# 990207_Schematic.net
KiCad netlist of a schematic drawn in Altium Designer
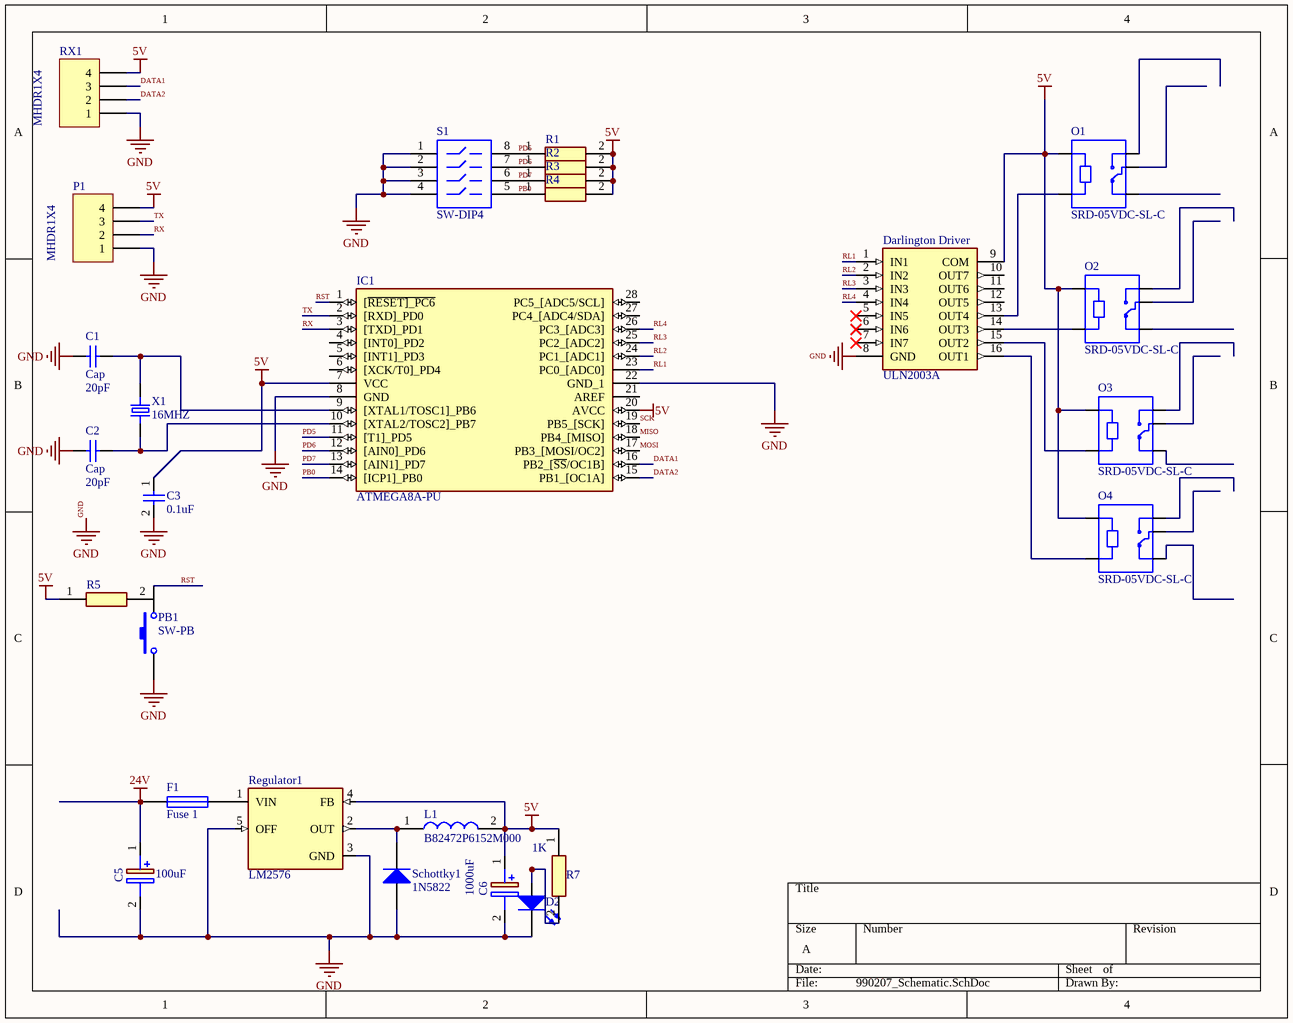
[diagram p0: 990207_Schematic.SchDoc]

(export (version "E")
  (design (tool "Eeschema 10.0.6"))
  (components
    (comp (ref "C1")
      (value "Cap")
      (footprint "RAD-0.3")
      (description "Capacitor")
      (fields (field (name "ALTIUM_VALUE") "20pF") (field (name "PUBLISHER") "Altium Limited"))
      (libsource (lib "Miscellaneous Devices") (part "Cap"))
    )
    (comp (ref "C2")
      (value "Cap")
      (footprint "RAD-0.3")
      (description "Capacitor")
      (fields (field (name "ALTIUM_VALUE") "20pF") (field (name "PUBLISHER") "Altium Limited"))
      (libsource (lib "Miscellaneous Devices") (part "Cap"))
    )
    (comp (ref "C3")
      (value "0.1uF")
      (footprint "RAD-0.3")
      (description "Capacitor")
      (fields (field (name "PUBLISHER") "Altium Limited"))
      (libsource (lib "") (part "Cap_1"))
    )
    (comp (ref "C5")
      (value "100uF")
      (footprint "SamacSys:CAPPRD550W60D1050H2150")
      (description "Capacitor Polarised")
      (fields (field (name "MANUFACTURER_PART_NUMBER") "108CKE025M"))
      (libsource (lib "*") (part "108CKE025M"))
    )
    (comp (ref "C6")
      (value "1000uF")
      (footprint "SamacSys:CAPPRD550W60D1050H2150")
      (description "Capacitor Polarised")
      (fields (field (name "MANUFACTURER_PART_NUMBER") "108CKE025M"))
      (libsource (lib "*") (part "108CKE025M"))
    )
    (comp (ref "D2")
      (value "LED0")
      (footprint "LED-0")
      (description "Typical INFRARED GaAs LED")
      (fields (field (name "PUBLISHER") "Altium Limited"))
      (libsource (lib "Miscellaneous Devices") (part "LED0"))
    )
    (comp (ref "Darlington Driver")
      (value "ULN2003A")
      (footprint "SamacSys:DIP794W56P254L1918H533Q16N")
      (description "Integrated Circuit")
      (fields (field (name "MOUSER PART NUMBER") "511-ULN2003A") (field (name "RS PART NUMBER") "6868209"))
      (libsource (lib "*") (part "ULN2003A"))
    )
    (comp (ref "F1")
      (value "Fuse 1")
      (footprint "PIN-W2/E2.8")
      (description "Fuse")
      (fields (field (name "PUBLISHER") "Altium Limited"))
      (libsource (lib "Miscellaneous Devices") (part "Fuse 1"))
    )
    (comp (ref "IC1")
      (value "ATMEGA8A-PU")
      (footprint "SamacSys:DIP794W53P254L3467H457Q28N")
      (description "Integrated Circuit")
      (fields
        (field (name "MOUSER PART NUMBER") "556-ATMEGA8A-PU")
        (field (name "RS PART NUMBER") "1310372P")
      )
      (libsource (lib "*") (part "ATMEGA8A-PU"))
    )
    (comp (ref "L1")
      (value "B82472P6152M000")
      (footprint "SamacSys:INDPM7474X450N")
      (description "Inductor")
      (fields (field (name "MOUSER PART NUMBER") "871-B82472P6152M000"))
      (libsource (lib "*") (part "B82472P6152M000"))
    )
    (comp (ref "O1")
      (value "SRD-05VDC-SL-C")
      (footprint "RELAY_SRD-05VDC-SL-C")
      (fields (field (name "MF") "Songle Relay"))
      (libsource (lib "SRD-05VDC-SL-C") (part "SRD-05VDC-SL-C"))
    )
    (comp (ref "O2")
      (value "SRD-05VDC-SL-C")
      (footprint "RELAY_SRD-05VDC-SL-C")
      (fields (field (name "MF") "Songle Relay"))
      (libsource (lib "SRD-05VDC-SL-C") (part "SRD-05VDC-SL-C"))
    )
    (comp (ref "O3")
      (value "SRD-05VDC-SL-C")
      (footprint "RELAY_SRD-05VDC-SL-C")
      (fields (field (name "MF") "Songle Relay"))
      (libsource (lib "SRD-05VDC-SL-C") (part "SRD-05VDC-SL-C"))
    )
    (comp (ref "O4")
      (value "SRD-05VDC-SL-C")
      (footprint "RELAY_SRD-05VDC-SL-C")
      (fields (field (name "MF") "Songle Relay"))
      (libsource (lib "SRD-05VDC-SL-C") (part "SRD-05VDC-SL-C"))
    )
    (comp (ref "P1")
      (value "MHDR1X4")
      (footprint "MHDR1X4")
      (description "Header, 4-Pin")
      (fields (field (name "PUBLISHER") "Altium Limited"))
      (libsource (lib "Miscellaneous Connectors") (part "MHDR1X4"))
    )
    (comp (ref "PB1")
      (value "SW-PB")
      (footprint "SPST-2")
      (description "Switch")
      (fields (field (name "PUBLISHER") "Altium Limited"))
      (libsource (lib "Miscellaneous Devices") (part "SW-PB"))
    )
    (comp (ref "R1")
      (value "CRCW120610M0FKEA")
      (footprint "SamacSys:RESC3216X60N")
      (description "Resistor")
      (fields (field (name "MOUSER PART NUMBER") "71-CRCW1206-10M-E3"))
      (libsource (lib "*") (part "CRCW120610M0FKEA"))
    )
    (comp (ref "R2")
      (value "CRCW120610M0FKEA")
      (footprint "SamacSys:RESC3216X60N")
      (description "Resistor")
      (fields (field (name "MOUSER PART NUMBER") "71-CRCW1206-10M-E3"))
      (libsource (lib "*") (part "CRCW120610M0FKEA"))
    )
    (comp (ref "R3")
      (value "CRCW120610M0FKEA")
      (footprint "SamacSys:RESC3216X60N")
      (description "Resistor")
      (fields (field (name "MOUSER PART NUMBER") "71-CRCW1206-10M-E3"))
      (libsource (lib "*") (part "CRCW120610M0FKEA"))
    )
    (comp (ref "R4")
      (value "CRCW120610M0FKEA")
      (footprint "SamacSys:RESC3216X60N")
      (description "Resistor")
      (fields (field (name "MOUSER PART NUMBER") "71-CRCW1206-10M-E3"))
      (libsource (lib "*") (part "CRCW120610M0FKEA"))
    )
    (comp (ref "R5")
      (value "CRCW120610M0FKEA")
      (footprint "SamacSys:RESC3216X60N")
      (description "Resistor")
      (fields (field (name "MOUSER PART NUMBER") "71-CRCW1206-10M-E3"))
      (libsource (lib "*") (part "CRCW120610M0FKEA"))
    )
    (comp (ref "R7")
      (value "1K")
      (footprint "SamacSys:RESC3216X60N")
      (description "Resistor")
      (fields
        (field (name "MANUFACTURER_PART_NUMBER") "CRCW120610M0FKEA")
        (field (name "MOUSER PART NUMBER") "71-CRCW1206-10M-E3")
      )
      (libsource (lib "") (part "CRCW120610M0FKEA_1"))
    )
    (comp (ref "Regulator1")
      (value "LM2576")
      (footprint "TO220-5")
      (fields (field (name "MF") "Texas Instruments"))
      (libsource (lib "LM2576") (part "LM2576"))
    )
    (comp (ref "RX1")
      (value "MHDR1X4")
      (footprint "MHDR1X4")
      (description "Header, 4-Pin")
      (fields (field (name "PUBLISHER") "Altium Limited"))
      (libsource (lib "Miscellaneous Connectors") (part "MHDR1X4"))
    )
    (comp (ref "S1")
      (value "SW-DIP4")
      (footprint "DIP-8")
      (description "DIP Switch")
      (fields (field (name "PUBLISHER") "Altium Limited"))
      (libsource (lib "Miscellaneous Devices") (part "SW-DIP4"))
    )
    (comp (ref "Schottky1")
      (value "1N5822")
      (footprint "DO-41")
      (description "1 Amp General Purpose Rectifier")
      (fields (field (name "PUBLISHER") "Altium Limited"))
      (libsource (lib "Miscellaneous Devices") (part "Diode 1N4001"))
    )
    (comp (ref "X1")
      (value "16MHZ")
      (footprint "XTAL_ABLS-8.000MHZ-B2-T")
      (description "8MHz Â±20ppm Crystal 18pF 80 Ohms HC-49/US")
      (fields (field (name "MP") "ABLS-8.000MHZ-B2") (field (name "MF") "Abracon LLC"))
      (libsource (lib "ABLS-8.000MHZ-B2-T") (part "ABLS-8.000MHZ-B2-T"))
    )
  )
  (nets
    (net (code "1") (name "/DATA1") (class "Default")
      (node (ref "IC1") (pin "16") (pinfunction "PB2_[~{SS}/OC1B]_16") (pintype "bidirectional"))
      (node (ref "RX1") (pin "3") (pinfunction "3_3") (pintype "passive"))
    )
    (net (code "2") (name "/DATA2") (class "Default")
      (node (ref "IC1") (pin "15") (pinfunction "PB1_[OC1A]_15") (pintype "bidirectional"))
      (node (ref "RX1") (pin "2") (pinfunction "2_2") (pintype "passive"))
    )
    (net (code "3") (name "/MISO") (class "Default")
      (node (ref "IC1") (pin "18") (pinfunction "PB4_[MISO]_18") (pintype "bidirectional"))
    )
    (net (code "4") (name "/MOSI") (class "Default")
      (node (ref "IC1") (pin "17") (pinfunction "PB3_[MOSI/OC2]_17") (pintype "bidirectional"))
    )
    (net (code "5") (name "/PB0") (class "Default")
      (node (ref "IC1") (pin "14") (pinfunction "[ICP1]_PB0_14") (pintype "bidirectional"))
      (node (ref "R4") (pin "1") (pinfunction "1_1") (pintype "passive"))
      (node (ref "S1") (pin "5") (pinfunction "5_5") (pintype "passive"))
    )
    (net (code "6") (name "/PD5") (class "Default")
      (node (ref "IC1") (pin "11") (pinfunction "[T1]_PD5_11") (pintype "bidirectional"))
      (node (ref "R1") (pin "1") (pinfunction "1_1") (pintype "passive"))
      (node (ref "S1") (pin "8") (pinfunction "8_8") (pintype "passive"))
    )
    (net (code "7") (name "/PD6") (class "Default")
      (node (ref "IC1") (pin "12") (pinfunction "[AIN0]_PD6_12") (pintype "bidirectional"))
      (node (ref "R2") (pin "1") (pinfunction "1_1") (pintype "passive"))
      (node (ref "S1") (pin "7") (pinfunction "7_7") (pintype "passive"))
    )
    (net (code "8") (name "/PD7") (class "Default")
      (node (ref "IC1") (pin "13") (pinfunction "[AIN1]_PD7_13") (pintype "bidirectional"))
      (node (ref "R3") (pin "1") (pinfunction "1_1") (pintype "passive"))
      (node (ref "S1") (pin "6") (pinfunction "6_6") (pintype "passive"))
    )
    (net (code "9") (name "/RL1") (class "Default")
      (node (ref "Darlington Driver") (pin "1") (pinfunction "IN1_1") (pintype "input"))
      (node (ref "IC1") (pin "23") (pinfunction "PC0_[ADC0]_23") (pintype "power_in"))
    )
    (net (code "10") (name "/RL2") (class "Default")
      (node (ref "Darlington Driver") (pin "2") (pinfunction "IN2_2") (pintype "input"))
      (node (ref "IC1") (pin "24") (pinfunction "PC1_[ADC1]_24") (pintype "bidirectional"))
    )
    (net (code "11") (name "/RL3") (class "Default")
      (node (ref "Darlington Driver") (pin "3") (pinfunction "IN3_3") (pintype "input"))
      (node (ref "IC1") (pin "25") (pinfunction "PC2_[ADC2]_25") (pintype "bidirectional"))
    )
    (net (code "12") (name "/RL4") (class "Default")
      (node (ref "Darlington Driver") (pin "4") (pinfunction "IN4_4") (pintype "input"))
      (node (ref "IC1") (pin "26") (pinfunction "PC3_[ADC3]_26") (pintype "bidirectional"))
    )
    (net (code "13") (name "/RST") (class "Default")
      (node (ref "IC1") (pin "1") (pinfunction "[~{RESET]_PC6}_1") (pintype "bidirectional"))
      (node (ref "PB1") (pin "2") (pinfunction "2_2") (pintype "passive"))
    )
    (net (code "14") (name "/RX") (class "Default")
      (node (ref "IC1") (pin "3") (pinfunction "[TXD]_PD1_3") (pintype "bidirectional"))
      (node (ref "P1") (pin "2") (pinfunction "2_2") (pintype "passive"))
    )
    (net (code "15") (name "/SCK") (class "Default")
      (node (ref "IC1") (pin "19") (pinfunction "PB5_[SCK]_19") (pintype "bidirectional"))
    )
    (net (code "16") (name "/TX") (class "Default")
      (node (ref "IC1") (pin "2") (pinfunction "[RXD]_PD0_2") (pintype "bidirectional"))
      (node (ref "P1") (pin "3") (pinfunction "3_3") (pintype "passive"))
    )
    (net (code "17") (name "5V") (class "Default")
      (node (ref "C3") (pin "1") (pinfunction "1_1") (pintype "passive"))
      (node (ref "C6") (pin "1") (pinfunction "+_1") (pintype "passive"))
      (node (ref "Darlington Driver") (pin "9") (pinfunction "COM_9") (pintype "passive"))
      (node (ref "IC1") (pin "20") (pinfunction "AVCC_20") (pintype "bidirectional"))
      (node (ref "IC1") (pin "7") (pinfunction "VCC_7") (pintype "power_in"))
      (node (ref "L1") (pin "2") (pinfunction "2_2") (pintype "passive"))
      (node (ref "O1") (pin "A1") (pinfunction "A1_A1") (pintype "passive"))
      (node (ref "O2") (pin "A1") (pinfunction "A1_A1") (pintype "passive"))
      (node (ref "O3") (pin "A1") (pinfunction "A1_A1") (pintype "passive"))
      (node (ref "O4") (pin "A1") (pinfunction "A1_A1") (pintype "passive"))
      (node (ref "P1") (pin "4") (pinfunction "4_4") (pintype "passive"))
      (node (ref "R1") (pin "2") (pinfunction "2_2") (pintype "passive"))
      (node (ref "R2") (pin "2") (pinfunction "2_2") (pintype "passive"))
      (node (ref "R3") (pin "2") (pinfunction "2_2") (pintype "passive"))
      (node (ref "R4") (pin "2") (pinfunction "2_2") (pintype "passive"))
      (node (ref "R5") (pin "1") (pinfunction "1_1") (pintype "passive"))
      (node (ref "R7") (pin "1") (pinfunction "1_1") (pintype "passive"))
      (node (ref "RX1") (pin "4") (pinfunction "4_4") (pintype "passive"))
      (node (ref "Regulator1") (pin "4") (pinfunction "FB_4") (pintype "input"))
    )
    (net (code "18") (name "24V") (class "Default")
      (node (ref "C5") (pin "1") (pinfunction "+_1") (pintype "passive"))
      (node (ref "F1") (pin "1") (pinfunction "1_1") (pintype "passive"))
    )
    (net (code "19") (name "GND") (class "Default")
      (node (ref "C1") (pin "1") (pinfunction "1_1") (pintype "passive"))
      (node (ref "C2") (pin "1") (pinfunction "1_1") (pintype "passive"))
      (node (ref "C3") (pin "2") (pinfunction "2_2") (pintype "passive"))
      (node (ref "C5") (pin "2") (pinfunction "-_2") (pintype "passive"))
      (node (ref "C6") (pin "2") (pinfunction "-_2") (pintype "passive"))
      (node (ref "D2") (pin "2") (pinfunction "K_2") (pintype "passive"))
      (node (ref "Darlington Driver") (pin "8") (pinfunction "GND_8") (pintype "power_in"))
      (node (ref "IC1") (pin "22") (pinfunction "GND_1_22") (pintype "power_in"))
      (node (ref "IC1") (pin "8") (pinfunction "GND_8") (pintype "power_in"))
      (node (ref "P1") (pin "1") (pinfunction "1_1") (pintype "passive"))
      (node (ref "PB1") (pin "1") (pinfunction "1_1") (pintype "passive"))
      (node (ref "RX1") (pin "1") (pinfunction "1_1") (pintype "passive"))
      (node (ref "Regulator1") (pin "3") (pinfunction "GND_3") (pintype "power_in"))
      (node (ref "Regulator1") (pin "5") (pinfunction "OFF_5") (pintype "input"))
      (node (ref "S1") (pin "1") (pinfunction "1_1") (pintype "passive"))
      (node (ref "S1") (pin "2") (pinfunction "2_2") (pintype "passive"))
      (node (ref "S1") (pin "3") (pinfunction "3_3") (pintype "passive"))
      (node (ref "S1") (pin "4") (pinfunction "4_4") (pintype "passive"))
      (node (ref "Schottky1") (pin "1") (pinfunction "A_1") (pintype "passive"))
    )
    (net (code "20") (name "Net-(D2-A)") (class "Default")
      (node (ref "D2") (pin "1") (pinfunction "A_1") (pintype "passive"))
      (node (ref "R7") (pin "2") (pinfunction "2_2") (pintype "passive"))
    )
    (net (code "21") (name "Net-(Darlington Driver-OUT1)") (class "Default")
      (node (ref "Darlington Driver") (pin "16") (pinfunction "OUT1_16") (pintype "output"))
      (node (ref "O4") (pin "A2") (pinfunction "A2_A2") (pintype "passive"))
    )
    (net (code "22") (name "Net-(Darlington Driver-OUT2)") (class "Default")
      (node (ref "Darlington Driver") (pin "15") (pinfunction "OUT2_15") (pintype "output"))
      (node (ref "O3") (pin "A2") (pinfunction "A2_A2") (pintype "passive"))
    )
    (net (code "23") (name "Net-(Darlington Driver-OUT3)") (class "Default")
      (node (ref "Darlington Driver") (pin "14") (pinfunction "OUT3_14") (pintype "output"))
      (node (ref "O2") (pin "A2") (pinfunction "A2_A2") (pintype "passive"))
    )
    (net (code "24") (name "Net-(Darlington Driver-OUT4)") (class "Default")
      (node (ref "Darlington Driver") (pin "13") (pinfunction "OUT4_13") (pintype "output"))
      (node (ref "O1") (pin "A2") (pinfunction "A2_A2") (pintype "passive"))
    )
    (net (code "25") (name "Net-(IC1-[XTAL1{slash}TOSC1]_PB6)") (class "Default")
      (node (ref "C1") (pin "2") (pinfunction "2_2") (pintype "passive"))
      (node (ref "IC1") (pin "9") (pinfunction "[XTAL1/TOSC1]_PB6_9") (pintype "bidirectional"))
      (node (ref "X1") (pin "2") (pinfunction "2_2") (pintype "passive"))
    )
    (net (code "26") (name "Net-(IC1-[XTAL2{slash}TOSC2]_PB7)") (class "Default")
      (node (ref "C2") (pin "2") (pinfunction "2_2") (pintype "passive"))
      (node (ref "IC1") (pin "10") (pinfunction "[XTAL2/TOSC2]_PB7_10") (pintype "bidirectional"))
      (node (ref "X1") (pin "1") (pinfunction "1_1") (pintype "passive"))
    )
    (net (code "27") (name "Net-(Regulator1-OUT)") (class "Default")
      (node (ref "L1") (pin "1") (pinfunction "1_1") (pintype "passive"))
      (node (ref "Regulator1") (pin "2") (pinfunction "OUT_2") (pintype "output"))
      (node (ref "Schottky1") (pin "2") (pinfunction "K_2") (pintype "passive"))
    )
    (net (code "28") (name "Net-(Regulator1-VIN)") (class "Default")
      (node (ref "F1") (pin "2") (pinfunction "2_2") (pintype "passive"))
      (node (ref "Regulator1") (pin "1") (pinfunction "VIN_1") (pintype "power_in"))
    )
    (net (code "29") (name "unconnected-(Darlington Driver-IN5-Pad5)") (class "Default")
      (node (ref "Darlington Driver") (pin "5") (pinfunction "IN5_5") (pintype "input+no_connect"))
    )
    (net (code "30") (name "unconnected-(Darlington Driver-IN6-Pad6)") (class "Default")
      (node (ref "Darlington Driver") (pin "6") (pinfunction "IN6_6") (pintype "input+no_connect"))
    )
    (net (code "31") (name "unconnected-(Darlington Driver-IN7-Pad7)") (class "Default")
      (node (ref "Darlington Driver") (pin "7") (pinfunction "IN7_7") (pintype "input+no_connect"))
    )
    (net (code "32") (name "unconnected-(Darlington Driver-OUT5-Pad12)") (class "Default")
      (node (ref "Darlington Driver") (pin "12") (pinfunction "OUT5_12") (pintype "output"))
    )
    (net (code "33") (name "unconnected-(Darlington Driver-OUT6-Pad11)") (class "Default")
      (node (ref "Darlington Driver") (pin "11") (pinfunction "OUT6_11") (pintype "output"))
    )
    (net (code "34") (name "unconnected-(Darlington Driver-OUT7-Pad10)") (class "Default")
      (node (ref "Darlington Driver") (pin "10") (pinfunction "OUT7_10") (pintype "output"))
    )
    (net (code "35") (name "unconnected-(IC1-AREF-Pad21)") (class "Default")
      (node (ref "IC1") (pin "21") (pinfunction "AREF_21") (pintype "power_in"))
    )
    (net (code "36") (name "unconnected-(IC1-PC4_[ADC4{slash}SDA]-Pad27)") (class "Default")
      (node (ref "IC1") (pin "27") (pinfunction "PC4_[ADC4/SDA]_27") (pintype "bidirectional"))
    )
    (net (code "37") (name "unconnected-(IC1-PC5_[ADC5{slash}SCL]-Pad28)") (class "Default")
      (node (ref "IC1") (pin "28") (pinfunction "PC5_[ADC5/SCL]_28") (pintype "bidirectional"))
    )
    (net (code "38") (name "unconnected-(IC1-[INT0]_PD2-Pad4)") (class "Default")
      (node (ref "IC1") (pin "4") (pinfunction "[INT0]_PD2_4") (pintype "bidirectional"))
    )
    (net (code "39") (name "unconnected-(IC1-[INT1]_PD3-Pad5)") (class "Default")
      (node (ref "IC1") (pin "5") (pinfunction "[INT1]_PD3_5") (pintype "bidirectional"))
    )
    (net (code "40") (name "unconnected-(IC1-[XCK{slash}T0]_PD4-Pad6)") (class "Default")
      (node (ref "IC1") (pin "6") (pinfunction "[XCK/T0]_PD4_6") (pintype "bidirectional"))
    )
    (net (code "41") (name "unconnected-(O1-PadCOM)") (class "Default")
      (node (ref "O1") (pin "COM") (pinfunction "COM_COM") (pintype "passive"))
    )
    (net (code "42") (name "unconnected-(O1-PadNC)") (class "Default")
      (node (ref "O1") (pin "NC") (pinfunction "NC_NC") (pintype "passive"))
    )
    (net (code "43") (name "unconnected-(O1-PadNO)") (class "Default")
      (node (ref "O1") (pin "NO") (pinfunction "NO_NO") (pintype "passive"))
    )
    (net (code "44") (name "unconnected-(O2-PadCOM)") (class "Default")
      (node (ref "O2") (pin "COM") (pinfunction "COM_COM") (pintype "passive"))
    )
    (net (code "45") (name "unconnected-(O2-PadNC)") (class "Default")
      (node (ref "O2") (pin "NC") (pinfunction "NC_NC") (pintype "passive"))
    )
    (net (code "46") (name "unconnected-(O2-PadNO)") (class "Default")
      (node (ref "O2") (pin "NO") (pinfunction "NO_NO") (pintype "passive"))
    )
    (net (code "47") (name "unconnected-(O3-PadCOM)") (class "Default")
      (node (ref "O3") (pin "COM") (pinfunction "COM_COM") (pintype "passive"))
    )
    (net (code "48") (name "unconnected-(O3-PadNC)") (class "Default")
      (node (ref "O3") (pin "NC") (pinfunction "NC_NC") (pintype "passive"))
    )
    (net (code "49") (name "unconnected-(O3-PadNO)") (class "Default")
      (node (ref "O3") (pin "NO") (pinfunction "NO_NO") (pintype "passive"))
    )
    (net (code "50") (name "unconnected-(O4-PadCOM)") (class "Default")
      (node (ref "O4") (pin "COM") (pinfunction "COM_COM") (pintype "passive"))
    )
    (net (code "51") (name "unconnected-(O4-PadNC)") (class "Default")
      (node (ref "O4") (pin "NC") (pinfunction "NC_NC") (pintype "passive"))
    )
    (net (code "52") (name "unconnected-(O4-PadNO)") (class "Default")
      (node (ref "O4") (pin "NO") (pinfunction "NO_NO") (pintype "passive"))
    )
    (net (code "53") (name "unconnected-(R5-Pad2)") (class "Default")
      (node (ref "R5") (pin "2") (pinfunction "2_2") (pintype "passive"))
    )
  )
)
